# isp.net
KiCad netlist of a schematic drawn in EAGLE
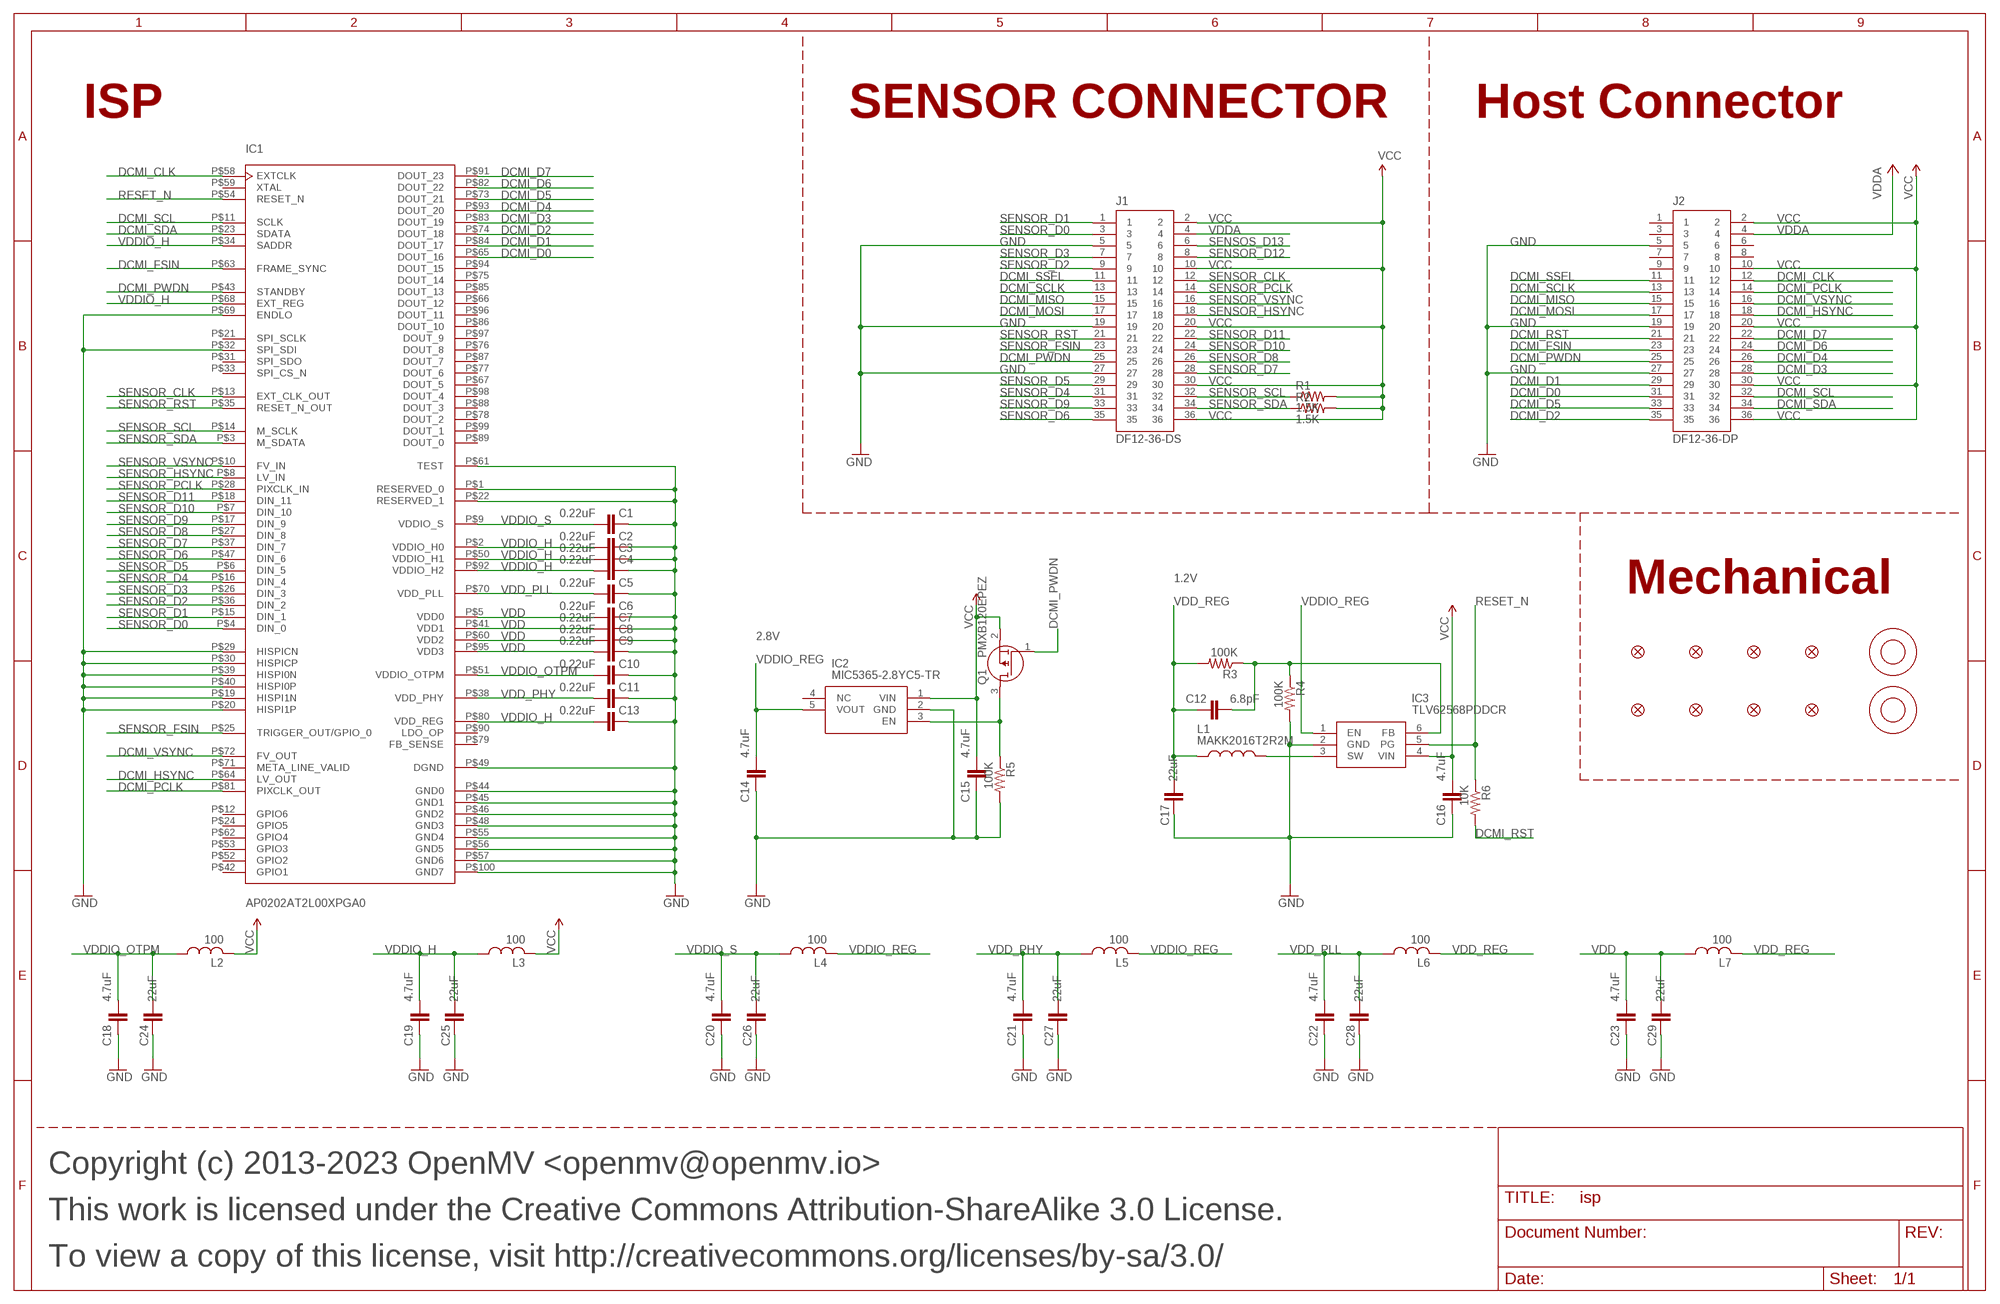
[diagram p0: schematic, sheet 1]

(export (version "E")
  (design (tool "Eeschema 10.0.6"))
  (components
    (comp (ref "C1")
      (value "0.22uF")
      (footprint "eagle-import:C0201")
      (fields (field (name "MPN") "GRM033R60J224ME15D"))
      (libsource (lib "eagle-import") (part "C-EUC0201"))
    )
    (comp (ref "C2")
      (value "0.22uF")
      (footprint "eagle-import:C0201")
      (fields (field (name "MPN") "GRM033R60J224ME15D"))
      (libsource (lib "eagle-import") (part "C-EUC0201"))
    )
    (comp (ref "C3")
      (value "0.22uF")
      (footprint "eagle-import:C0201")
      (fields (field (name "MPN") "GRM033R60J224ME15D"))
      (libsource (lib "eagle-import") (part "C-EUC0201"))
    )
    (comp (ref "C4")
      (value "0.22uF")
      (footprint "eagle-import:C0201")
      (fields (field (name "MPN") "GRM033R60J224ME15D"))
      (libsource (lib "eagle-import") (part "C-EUC0201"))
    )
    (comp (ref "C5")
      (value "0.22uF")
      (footprint "eagle-import:C0201")
      (fields (field (name "MPN") "GRM033R60J224ME15D"))
      (libsource (lib "eagle-import") (part "C-EUC0201"))
    )
    (comp (ref "C6")
      (value "0.22uF")
      (footprint "eagle-import:C0201")
      (fields (field (name "MPN") "GRM033R60J224ME15D"))
      (libsource (lib "eagle-import") (part "C-EUC0201"))
    )
    (comp (ref "C7")
      (value "0.22uF")
      (footprint "eagle-import:C0201")
      (fields (field (name "MPN") "GRM033R60J224ME15D"))
      (libsource (lib "eagle-import") (part "C-EUC0201"))
    )
    (comp (ref "C8")
      (value "0.22uF")
      (footprint "eagle-import:C0201")
      (fields (field (name "MPN") "GRM033R60J224ME15D"))
      (libsource (lib "eagle-import") (part "C-EUC0201"))
    )
    (comp (ref "C9")
      (value "0.22uF")
      (footprint "eagle-import:C0201")
      (fields (field (name "MPN") "GRM033R60J224ME15D"))
      (libsource (lib "eagle-import") (part "C-EUC0201"))
    )
    (comp (ref "C10")
      (value "0.22uF")
      (footprint "eagle-import:C0201")
      (fields (field (name "MPN") "GRM033R60J224ME15D"))
      (libsource (lib "eagle-import") (part "C-EUC0201"))
    )
    (comp (ref "C11")
      (value "0.22uF")
      (footprint "eagle-import:C0201")
      (fields (field (name "MPN") "GRM033R60J224ME15D"))
      (libsource (lib "eagle-import") (part "C-EUC0201"))
    )
    (comp (ref "C12")
      (value "6.8pF")
      (footprint "eagle-import:0402")
      (fields (field (name "MPN") "GRM1555C1H6R8DA01D"))
      (libsource (lib "eagle-import") (part "CAP_0402"))
    )
    (comp (ref "C13")
      (value "0.22uF")
      (footprint "eagle-import:C0201")
      (fields (field (name "MPN") "GRM033R60J224ME15D"))
      (libsource (lib "eagle-import") (part "C-EUC0201"))
    )
    (comp (ref "C14")
      (value "4.7uF")
      (footprint "eagle-import:0402")
      (fields (field (name "MPN") "JMK105BBJ475MV-F"))
      (libsource (lib "eagle-import") (part "CAP_0402"))
    )
    (comp (ref "C15")
      (value "4.7uF")
      (footprint "eagle-import:0402")
      (fields (field (name "MPN") "JMK105BBJ475MV-F"))
      (libsource (lib "eagle-import") (part "CAP_0402"))
    )
    (comp (ref "C16")
      (value "4.7uF")
      (footprint "eagle-import:0402")
      (fields (field (name "MPN") "JMK105BBJ475MV-F"))
      (libsource (lib "eagle-import") (part "CAP_0402"))
    )
    (comp (ref "C17")
      (value "22uF")
      (footprint "eagle-import:0805")
      (fields (field (name "MPN") "CL21A226MQQNNNE"))
      (libsource (lib "eagle-import") (part "22UF-0805-6.3V-20%"))
    )
    (comp (ref "C18")
      (value "4.7uF")
      (footprint "eagle-import:0402")
      (fields (field (name "MPN") "JMK105BBJ475MV-F"))
      (libsource (lib "eagle-import") (part "CAP_0402"))
    )
    (comp (ref "C19")
      (value "4.7uF")
      (footprint "eagle-import:0402")
      (fields (field (name "MPN") "JMK105BBJ475MV-F"))
      (libsource (lib "eagle-import") (part "CAP_0402"))
    )
    (comp (ref "C20")
      (value "4.7uF")
      (footprint "eagle-import:0402")
      (fields (field (name "MPN") "JMK105BBJ475MV-F"))
      (libsource (lib "eagle-import") (part "CAP_0402"))
    )
    (comp (ref "C21")
      (value "4.7uF")
      (footprint "eagle-import:0402")
      (fields (field (name "MPN") "JMK105BBJ475MV-F"))
      (libsource (lib "eagle-import") (part "CAP_0402"))
    )
    (comp (ref "C22")
      (value "4.7uF")
      (footprint "eagle-import:0402")
      (fields (field (name "MPN") "JMK105BBJ475MV-F"))
      (libsource (lib "eagle-import") (part "CAP_0402"))
    )
    (comp (ref "C23")
      (value "4.7uF")
      (footprint "eagle-import:0402")
      (fields (field (name "MPN") "JMK105BBJ475MV-F"))
      (libsource (lib "eagle-import") (part "CAP_0402"))
    )
    (comp (ref "C24")
      (value "22uF")
      (footprint "eagle-import:0805")
      (fields (field (name "MPN") "CL21A226MQQNNNE"))
      (libsource (lib "eagle-import") (part "22UF-0805-6.3V-20%"))
    )
    (comp (ref "C25")
      (value "22uF")
      (footprint "eagle-import:0805")
      (fields (field (name "MPN") "CL21A226MQQNNNE"))
      (libsource (lib "eagle-import") (part "22UF-0805-6.3V-20%"))
    )
    (comp (ref "C26")
      (value "22uF")
      (footprint "eagle-import:0805")
      (fields (field (name "MPN") "CL21A226MQQNNNE"))
      (libsource (lib "eagle-import") (part "22UF-0805-6.3V-20%"))
    )
    (comp (ref "C27")
      (value "22uF")
      (footprint "eagle-import:0805")
      (fields (field (name "MPN") "CL21A226MQQNNNE"))
      (libsource (lib "eagle-import") (part "22UF-0805-6.3V-20%"))
    )
    (comp (ref "C28")
      (value "22uF")
      (footprint "eagle-import:0805")
      (fields (field (name "MPN") "CL21A226MQQNNNE"))
      (libsource (lib "eagle-import") (part "22UF-0805-6.3V-20%"))
    )
    (comp (ref "C29")
      (value "22uF")
      (footprint "eagle-import:0805")
      (fields (field (name "MPN") "CL21A226MQQNNNE"))
      (libsource (lib "eagle-import") (part "22UF-0805-6.3V-20%"))
    )
    (comp (ref "FD1")
      (value "FIDUCIAL1X2")
      (footprint "eagle-import:FIDUCIAL-1X2")
      (libsource (lib "eagle-import") (part "FIDUCIAL1X2"))
    )
    (comp (ref "FD2")
      (value "FIDUCIAL1X2")
      (footprint "eagle-import:FIDUCIAL-1X2")
      (libsource (lib "eagle-import") (part "FIDUCIAL1X2"))
    )
    (comp (ref "FD3")
      (value "FIDUCIAL1X2")
      (footprint "eagle-import:FIDUCIAL-1X2")
      (libsource (lib "eagle-import") (part "FIDUCIAL1X2"))
    )
    (comp (ref "FD4")
      (value "FIDUCIAL1X2")
      (footprint "eagle-import:FIDUCIAL-1X2")
      (libsource (lib "eagle-import") (part "FIDUCIAL1X2"))
    )
    (comp (ref "FD5")
      (value "FIDUCIAL1X2")
      (footprint "eagle-import:FIDUCIAL-1X2")
      (libsource (lib "eagle-import") (part "FIDUCIAL1X2"))
    )
    (comp (ref "FD6")
      (value "FIDUCIAL1X2")
      (footprint "eagle-import:FIDUCIAL-1X2")
      (libsource (lib "eagle-import") (part "FIDUCIAL1X2"))
    )
    (comp (ref "FD7")
      (value "FIDUCIAL1X2")
      (footprint "eagle-import:FIDUCIAL-1X2")
      (libsource (lib "eagle-import") (part "FIDUCIAL1X2"))
    )
    (comp (ref "FD8")
      (value "FIDUCIAL1X2")
      (footprint "eagle-import:FIDUCIAL-1X2")
      (libsource (lib "eagle-import") (part "FIDUCIAL1X2"))
    )
    (comp (ref "IC1")
      (value "AP0202AT2L00XPGA0")
      (footprint "eagle-import:AP0202AT2L00XPGA0")
      (fields (field (name "MPN") "AP0202AT2L00XPGA0-DR"))
      (libsource (lib "eagle-import") (part "AP0202AT2L00XPGA0"))
    )
    (comp (ref "IC2")
      (value "MIC5365-2.8YC5-TR")
      (footprint "eagle-import:SOT65P210X110-5N")
      (fields (field (name "MOUSER_PART_NUMBER") "998-MIC5365-2.8YC5TR"))
      (libsource (lib "eagle-import") (part "MIC5365-2.8YC5-TR"))
    )
    (comp (ref "IC3")
      (value "TLV62568PDDCR")
      (footprint "eagle-import:SOT95P280X110-6N")
      (fields (field (name "MOUSER_PART_NUMBER") "595-TLV62568PDDCR"))
      (libsource (lib "eagle-import") (part "TLV62568PDDCR"))
    )
    (comp (ref "J1")
      (value "DF12-36-DS")
      (footprint "eagle-import:DF12-36-DS")
      (fields (field (name "MPN") "DF12NB-36DS-0.5V(51)"))
      (libsource (lib "eagle-import") (part "DF12-36-DS"))
    )
    (comp (ref "J2")
      (value "DF12-36-DP")
      (footprint "eagle-import:DF12-36-DP")
      (fields (field (name "MPN") "DF12NB(3.0)-36DP-0.5V(51)"))
      (libsource (lib "eagle-import") (part "DF12-36-DP"))
    )
    (comp (ref "L1")
      (value "MAKK2016T2R2M")
      (footprint "eagle-import:INDC2016X100N")
      (fields (field (name "MF") "Taiyo Yuden"))
      (libsource (lib "eagle-import") (part "MAKK2016T2R2M"))
    )
    (comp (ref "L2")
      (value "100")
      (footprint "eagle-import:0402")
      (fields (field (name "MPN") "MFBM1V1005-101-R"))
      (libsource (lib "eagle-import") (part "INDUCTOR_0402"))
    )
    (comp (ref "L3")
      (value "100")
      (footprint "eagle-import:0402")
      (fields (field (name "MPN") "MFBM1V1005-101-R"))
      (libsource (lib "eagle-import") (part "INDUCTOR_0402"))
    )
    (comp (ref "L4")
      (value "100")
      (footprint "eagle-import:0402")
      (fields (field (name "MPN") "MFBM1V1005-101-R"))
      (libsource (lib "eagle-import") (part "INDUCTOR_0402"))
    )
    (comp (ref "L5")
      (value "100")
      (footprint "eagle-import:0402")
      (fields (field (name "MPN") "MFBM1V1005-101-R"))
      (libsource (lib "eagle-import") (part "INDUCTOR_0402"))
    )
    (comp (ref "L6")
      (value "100")
      (footprint "eagle-import:0402")
      (fields (field (name "MPN") "MFBM1V1005-101-R"))
      (libsource (lib "eagle-import") (part "INDUCTOR_0402"))
    )
    (comp (ref "L7")
      (value "100")
      (footprint "eagle-import:0402")
      (fields (field (name "MPN") "MFBM1V1005-101-R"))
      (libsource (lib "eagle-import") (part "INDUCTOR_0402"))
    )
    (comp (ref "M1")
      (value "9774030151R")
      (footprint "eagle-import:9774030151R")
      (libsource (lib "eagle-import") (part "9774030151R"))
    )
    (comp (ref "M2")
      (value "9774030151R")
      (footprint "eagle-import:9774030151R")
      (libsource (lib "eagle-import") (part "9774030151R"))
    )
    (comp (ref "Q1")
      (value "PMXB120EPEZ")
      (footprint "eagle-import:PMXB120EPEZ")
      (fields (field (name "MOUSER_PART_NUMBER") "771-PMXB120EPEZ"))
      (libsource (lib "eagle-import") (part "PMXB120EPEZ"))
    )
    (comp (ref "R1")
      (value "1.5K")
      (footprint "eagle-import:R0402")
      (fields (field (name "MPN") "RC0402FR-131K5L"))
      (libsource (lib "eagle-import") (part "R-US_R0402"))
    )
    (comp (ref "R2")
      (value "1.5K")
      (footprint "eagle-import:R0402")
      (fields (field (name "MPN") "RC0402FR-131K5L"))
      (libsource (lib "eagle-import") (part "R-US_R0402"))
    )
    (comp (ref "R3")
      (value "100K")
      (footprint "eagle-import:R0402")
      (fields (field (name "MPN") "AC0402FR-07100KL"))
      (libsource (lib "eagle-import") (part "R-US_R0402"))
    )
    (comp (ref "R4")
      (value "100K")
      (footprint "eagle-import:R0402")
      (fields (field (name "MPN") "AC0402FR-07100KL"))
      (libsource (lib "eagle-import") (part "R-US_R0402"))
    )
    (comp (ref "R5")
      (value "100K")
      (footprint "eagle-import:R0402")
      (fields (field (name "MPN") "AC0402FR-07100KL"))
      (libsource (lib "eagle-import") (part "R-US_R0402"))
    )
    (comp (ref "R6")
      (value "10K")
      (footprint "eagle-import:R0402")
      (fields (field (name "MPN") "AC0402FR-1310KL"))
      (libsource (lib "eagle-import") (part "R-US_R0402"))
    )
  )
  (nets
    (net (code "1") (name "/DCMI_CLK") (class "Default")
      (node (ref "IC1") (pin "P$58") (pinfunction "EXTCLK_P$58") (pintype "input"))
      (node (ref "J2") (pin "12") (pinfunction "12_12") (pintype "bidirectional"))
    )
    (net (code "2") (name "/DCMI_D0") (class "Default")
      (node (ref "IC1") (pin "P$65") (pinfunction "DOUT_16_P$65") (pintype "output"))
      (node (ref "J2") (pin "31") (pinfunction "31_31") (pintype "bidirectional"))
    )
    (net (code "3") (name "/DCMI_D1") (class "Default")
      (node (ref "IC1") (pin "P$84") (pinfunction "DOUT_17_P$84") (pintype "output"))
      (node (ref "J2") (pin "29") (pinfunction "29_29") (pintype "bidirectional"))
    )
    (net (code "4") (name "/DCMI_D2") (class "Default")
      (node (ref "IC1") (pin "P$74") (pinfunction "DOUT_18_P$74") (pintype "output"))
      (node (ref "J2") (pin "35") (pinfunction "35_35") (pintype "bidirectional"))
    )
    (net (code "5") (name "/DCMI_D3") (class "Default")
      (node (ref "IC1") (pin "P$83") (pinfunction "DOUT_19_P$83") (pintype "output"))
      (node (ref "J2") (pin "28") (pinfunction "28_28") (pintype "bidirectional"))
    )
    (net (code "6") (name "/DCMI_D4") (class "Default")
      (node (ref "IC1") (pin "P$93") (pinfunction "DOUT_20_P$93") (pintype "output"))
      (node (ref "J2") (pin "26") (pinfunction "26_26") (pintype "bidirectional"))
    )
    (net (code "7") (name "/DCMI_D5") (class "Default")
      (node (ref "IC1") (pin "P$73") (pinfunction "DOUT_21_P$73") (pintype "output"))
      (node (ref "J2") (pin "33") (pinfunction "33_33") (pintype "bidirectional"))
    )
    (net (code "8") (name "/DCMI_D6") (class "Default")
      (node (ref "IC1") (pin "P$82") (pinfunction "DOUT_22_P$82") (pintype "output"))
      (node (ref "J2") (pin "24") (pinfunction "24_24") (pintype "bidirectional"))
    )
    (net (code "9") (name "/DCMI_D7") (class "Default")
      (node (ref "IC1") (pin "P$91") (pinfunction "DOUT_23_P$91") (pintype "output"))
      (node (ref "J2") (pin "22") (pinfunction "22_22") (pintype "bidirectional"))
    )
    (net (code "10") (name "/DCMI_FSIN") (class "Default")
      (node (ref "IC1") (pin "P$63") (pinfunction "FRAME_SYNC_P$63") (pintype "input"))
      (node (ref "J2") (pin "23") (pinfunction "23_23") (pintype "bidirectional"))
    )
    (net (code "11") (name "/DCMI_HSYNC") (class "Default")
      (node (ref "IC1") (pin "P$64") (pinfunction "LV_OUT_P$64") (pintype "output"))
      (node (ref "J2") (pin "18") (pinfunction "18_18") (pintype "bidirectional"))
    )
    (net (code "12") (name "/DCMI_MISO") (class "Default")
      (node (ref "J1") (pin "15") (pinfunction "15_15") (pintype "bidirectional"))
      (node (ref "J2") (pin "15") (pinfunction "15_15") (pintype "bidirectional"))
    )
    (net (code "13") (name "/DCMI_MOSI") (class "Default")
      (node (ref "J1") (pin "17") (pinfunction "17_17") (pintype "bidirectional"))
      (node (ref "J2") (pin "17") (pinfunction "17_17") (pintype "bidirectional"))
    )
    (net (code "14") (name "/DCMI_PCLK") (class "Default")
      (node (ref "IC1") (pin "P$81") (pinfunction "PIXCLK_OUT_P$81") (pintype "output"))
      (node (ref "J2") (pin "14") (pinfunction "14_14") (pintype "bidirectional"))
    )
    (net (code "15") (name "/DCMI_PWDN") (class "Default")
      (node (ref "IC1") (pin "P$43") (pinfunction "STANDBY_P$43") (pintype "input"))
      (node (ref "J1") (pin "25") (pinfunction "25_25") (pintype "bidirectional"))
      (node (ref "J2") (pin "25") (pinfunction "25_25") (pintype "bidirectional"))
      (node (ref "Q1") (pin "1") (pinfunction "G_1") (pintype "bidirectional"))
    )
    (net (code "16") (name "/DCMI_RST") (class "Default")
      (node (ref "J2") (pin "21") (pinfunction "21_21") (pintype "bidirectional"))
      (node (ref "R6") (pin "2") (pinfunction "2_2") (pintype "passive"))
    )
    (net (code "17") (name "/DCMI_SCL") (class "Default")
      (node (ref "IC1") (pin "P$11") (pinfunction "SCLK_P$11") (pintype "input"))
      (node (ref "J2") (pin "32") (pinfunction "32_32") (pintype "bidirectional"))
    )
    (net (code "18") (name "/DCMI_SCLK") (class "Default")
      (node (ref "J1") (pin "13") (pinfunction "13_13") (pintype "bidirectional"))
      (node (ref "J2") (pin "13") (pinfunction "13_13") (pintype "bidirectional"))
    )
    (net (code "19") (name "/DCMI_SDA") (class "Default")
      (node (ref "IC1") (pin "P$23") (pinfunction "SDATA_P$23") (pintype "bidirectional"))
      (node (ref "J2") (pin "34") (pinfunction "34_34") (pintype "bidirectional"))
    )
    (net (code "20") (name "/DCMI_SSEL") (class "Default")
      (node (ref "J1") (pin "11") (pinfunction "11_11") (pintype "bidirectional"))
      (node (ref "J2") (pin "11") (pinfunction "11_11") (pintype "bidirectional"))
    )
    (net (code "21") (name "/DCMI_VSYNC") (class "Default")
      (node (ref "IC1") (pin "P$72") (pinfunction "FV_OUT_P$72") (pintype "output"))
      (node (ref "J2") (pin "16") (pinfunction "16_16") (pintype "bidirectional"))
    )
    (net (code "22") (name "/RESET_N") (class "Default")
      (node (ref "IC1") (pin "P$54") (pinfunction "RESET_N_P$54") (pintype "input"))
      (node (ref "IC3") (pin "5") (pinfunction "PG_5") (pintype "bidirectional"))
      (node (ref "R6") (pin "1") (pinfunction "1_1") (pintype "passive"))
    )
    (net (code "23") (name "/SENSOR_CLK") (class "Default")
      (node (ref "IC1") (pin "P$13") (pinfunction "EXT_CLK_OUT_P$13") (pintype "output"))
      (node (ref "J1") (pin "12") (pinfunction "12_12") (pintype "bidirectional"))
    )
    (net (code "24") (name "/SENSOR_D0") (class "Default")
      (node (ref "IC1") (pin "P$4") (pinfunction "DIN_0_P$4") (pintype "input"))
      (node (ref "J1") (pin "3") (pinfunction "3_3") (pintype "bidirectional"))
    )
    (net (code "25") (name "/SENSOR_D1") (class "Default")
      (node (ref "IC1") (pin "P$15") (pinfunction "DIN_1_P$15") (pintype "input"))
      (node (ref "J1") (pin "1") (pinfunction "1_1") (pintype "bidirectional"))
    )
    (net (code "26") (name "/SENSOR_D2") (class "Default")
      (node (ref "IC1") (pin "P$36") (pinfunction "DIN_2_P$36") (pintype "input"))
      (node (ref "J1") (pin "9") (pinfunction "9_9") (pintype "bidirectional"))
    )
    (net (code "27") (name "/SENSOR_D3") (class "Default")
      (node (ref "IC1") (pin "P$26") (pinfunction "DIN_3_P$26") (pintype "input"))
      (node (ref "J1") (pin "7") (pinfunction "7_7") (pintype "bidirectional"))
    )
    (net (code "28") (name "/SENSOR_D4") (class "Default")
      (node (ref "IC1") (pin "P$16") (pinfunction "DIN_4_P$16") (pintype "input"))
      (node (ref "J1") (pin "31") (pinfunction "31_31") (pintype "bidirectional"))
    )
    (net (code "29") (name "/SENSOR_D5") (class "Default")
      (node (ref "IC1") (pin "P$6") (pinfunction "DIN_5_P$6") (pintype "input"))
      (node (ref "J1") (pin "29") (pinfunction "29_29") (pintype "bidirectional"))
    )
    (net (code "30") (name "/SENSOR_D6") (class "Default")
      (node (ref "IC1") (pin "P$47") (pinfunction "DIN_6_P$47") (pintype "input"))
      (node (ref "J1") (pin "35") (pinfunction "35_35") (pintype "bidirectional"))
    )
    (net (code "31") (name "/SENSOR_D7") (class "Default")
      (node (ref "IC1") (pin "P$37") (pinfunction "DIN_7_P$37") (pintype "input"))
      (node (ref "J1") (pin "28") (pinfunction "28_28") (pintype "bidirectional"))
    )
    (net (code "32") (name "/SENSOR_D8") (class "Default")
      (node (ref "IC1") (pin "P$27") (pinfunction "DIN_8_P$27") (pintype "input"))
      (node (ref "J1") (pin "26") (pinfunction "26_26") (pintype "bidirectional"))
    )
    (net (code "33") (name "/SENSOR_D9") (class "Default")
      (node (ref "IC1") (pin "P$17") (pinfunction "DIN_9_P$17") (pintype "input"))
      (node (ref "J1") (pin "33") (pinfunction "33_33") (pintype "bidirectional"))
    )
    (net (code "34") (name "/SENSOR_D10") (class "Default")
      (node (ref "IC1") (pin "P$7") (pinfunction "DIN_10_P$7") (pintype "input"))
      (node (ref "J1") (pin "24") (pinfunction "24_24") (pintype "bidirectional"))
    )
    (net (code "35") (name "/SENSOR_D11") (class "Default")
      (node (ref "IC1") (pin "P$18") (pinfunction "DIN_11_P$18") (pintype "input"))
      (node (ref "J1") (pin "22") (pinfunction "22_22") (pintype "bidirectional"))
    )
    (net (code "36") (name "/SENSOR_D12") (class "Default")
      (node (ref "J1") (pin "8") (pinfunction "8_8") (pintype "bidirectional"))
    )
    (net (code "37") (name "/SENSOR_FSIN") (class "Default")
      (node (ref "IC1") (pin "P$25") (pinfunction "TRIGGER_OUT/GPIO_0_P$25") (pintype "output"))
      (node (ref "J1") (pin "23") (pinfunction "23_23") (pintype "bidirectional"))
    )
    (net (code "38") (name "/SENSOR_HSYNC") (class "Default")
      (node (ref "IC1") (pin "P$8") (pinfunction "LV_IN_P$8") (pintype "input"))
      (node (ref "J1") (pin "18") (pinfunction "18_18") (pintype "bidirectional"))
    )
    (net (code "39") (name "/SENSOR_PCLK") (class "Default")
      (node (ref "IC1") (pin "P$28") (pinfunction "PIXCLK_IN_P$28") (pintype "input"))
      (node (ref "J1") (pin "14") (pinfunction "14_14") (pintype "bidirectional"))
    )
    (net (code "40") (name "/SENSOR_RST") (class "Default")
      (node (ref "IC1") (pin "P$35") (pinfunction "RESET_N_OUT_P$35") (pintype "output"))
      (node (ref "J1") (pin "21") (pinfunction "21_21") (pintype "bidirectional"))
    )
    (net (code "41") (name "/SENSOR_SCL") (class "Default")
      (node (ref "IC1") (pin "P$14") (pinfunction "M_SCLK_P$14") (pintype "output"))
      (node (ref "J1") (pin "32") (pinfunction "32_32") (pintype "bidirectional"))
      (node (ref "R1") (pin "1") (pinfunction "1_1") (pintype "passive"))
    )
    (net (code "42") (name "/SENSOR_SDA") (class "Default")
      (node (ref "IC1") (pin "P$3") (pinfunction "M_SDATA_P$3") (pintype "bidirectional"))
      (node (ref "J1") (pin "34") (pinfunction "34_34") (pintype "bidirectional"))
      (node (ref "R2") (pin "1") (pinfunction "1_1") (pintype "passive"))
    )
    (net (code "43") (name "/SENSOR_VSYNC") (class "Default")
      (node (ref "IC1") (pin "P$10") (pinfunction "FV_IN_P$10") (pintype "input"))
      (node (ref "J1") (pin "16") (pinfunction "16_16") (pintype "bidirectional"))
    )
    (net (code "44") (name "/SENSOS_D13") (class "Default")
      (node (ref "J1") (pin "6") (pinfunction "6_6") (pintype "bidirectional"))
    )
    (net (code "45") (name "/VDD") (class "Default")
      (node (ref "C23") (pin "2") (pinfunction "2_2") (pintype "passive"))
      (node (ref "C29") (pin "2") (pinfunction "2_2") (pintype "passive"))
      (node (ref "C6") (pin "2") (pinfunction "2_2") (pintype "passive"))
      (node (ref "C7") (pin "2") (pinfunction "2_2") (pintype "passive"))
      (node (ref "C8") (pin "2") (pinfunction "2_2") (pintype "passive"))
      (node (ref "C9") (pin "2") (pinfunction "2_2") (pintype "passive"))
      (node (ref "IC1") (pin "P$41") (pinfunction "VDD1_P$41") (pintype "power_in"))
      (node (ref "IC1") (pin "P$5") (pinfunction "VDD0_P$5") (pintype "power_in"))
      (node (ref "IC1") (pin "P$60") (pinfunction "VDD2_P$60") (pintype "power_in"))
      (node (ref "IC1") (pin "P$95") (pinfunction "VDD3_P$95") (pintype "power_in"))
      (node (ref "L7") (pin "1") (pinfunction "P$1_1") (pintype "passive"))
    )
    (net (code "46") (name "/VDDIO_H") (class "Default")
      (node (ref "C13") (pin "2") (pinfunction "2_2") (pintype "passive"))
      (node (ref "C19") (pin "2") (pinfunction "2_2") (pintype "passive"))
      (node (ref "C2") (pin "2") (pinfunction "2_2") (pintype "passive"))
      (node (ref "C25") (pin "2") (pinfunction "2_2") (pintype "passive"))
      (node (ref "C3") (pin "2") (pinfunction "2_2") (pintype "passive"))
      (node (ref "C4") (pin "2") (pinfunction "2_2") (pintype "passive"))
      (node (ref "IC1") (pin "P$2") (pinfunction "VDDIO_H0_P$2") (pintype "power_in"))
      (node (ref "IC1") (pin "P$34") (pinfunction "SADDR_P$34") (pintype "input"))
      (node (ref "IC1") (pin "P$50") (pinfunction "VDDIO_H1_P$50") (pintype "power_in"))
      (node (ref "IC1") (pin "P$68") (pinfunction "EXT_REG_P$68") (pintype "input"))
      (node (ref "IC1") (pin "P$80") (pinfunction "VDD_REG_P$80") (pintype "power_in"))
      (node (ref "IC1") (pin "P$92") (pinfunction "VDDIO_H2_P$92") (pintype "power_in"))
      (node (ref "L3") (pin "1") (pinfunction "P$1_1") (pintype "passive"))
    )
    (net (code "47") (name "/VDDIO_OTPM") (class "Default")
      (node (ref "C10") (pin "2") (pinfunction "2_2") (pintype "passive"))
      (node (ref "C18") (pin "2") (pinfunction "2_2") (pintype "passive"))
      (node (ref "C24") (pin "2") (pinfunction "2_2") (pintype "passive"))
      (node (ref "IC1") (pin "P$51") (pinfunction "VDDIO_OTPM_P$51") (pintype "power_in"))
      (node (ref "L2") (pin "1") (pinfunction "P$1_1") (pintype "passive"))
    )
    (net (code "48") (name "/VDDIO_REG") (class "Default")
      (node (ref "C14") (pin "2") (pinfunction "2_2") (pintype "passive"))
      (node (ref "IC2") (pin "5") (pinfunction "VOUT_5") (pintype "bidirectional"))
      (node (ref "IC3") (pin "1") (pinfunction "EN_1") (pintype "bidirectional"))
      (node (ref "L4") (pin "2") (pinfunction "P$2_2") (pintype "passive"))
      (node (ref "L5") (pin "2") (pinfunction "P$2_2") (pintype "passive"))
    )
    (net (code "49") (name "/VDDIO_S") (class "Default")
      (node (ref "C1") (pin "2") (pinfunction "2_2") (pintype "passive"))
      (node (ref "C20") (pin "2") (pinfunction "2_2") (pintype "passive"))
      (node (ref "C26") (pin "2") (pinfunction "2_2") (pintype "passive"))
      (node (ref "IC1") (pin "P$9") (pinfunction "VDDIO_S_P$9") (pintype "power_in"))
      (node (ref "L4") (pin "1") (pinfunction "P$1_1") (pintype "passive"))
    )
    (net (code "50") (name "/VDD_PHY") (class "Default")
      (node (ref "C11") (pin "2") (pinfunction "2_2") (pintype "passive"))
      (node (ref "C21") (pin "2") (pinfunction "2_2") (pintype "passive"))
      (node (ref "C27") (pin "2") (pinfunction "2_2") (pintype "passive"))
      (node (ref "IC1") (pin "P$38") (pinfunction "VDD_PHY_P$38") (pintype "power_in"))
      (node (ref "L5") (pin "1") (pinfunction "P$1_1") (pintype "passive"))
    )
    (net (code "51") (name "/VDD_PLL") (class "Default")
      (node (ref "C22") (pin "2") (pinfunction "2_2") (pintype "passive"))
      (node (ref "C28") (pin "2") (pinfunction "2_2") (pintype "passive"))
      (node (ref "C5") (pin "2") (pinfunction "2_2") (pintype "passive"))
      (node (ref "IC1") (pin "P$70") (pinfunction "VDD_PLL_P$70") (pintype "power_in"))
      (node (ref "L6") (pin "1") (pinfunction "P$1_1") (pintype "passive"))
    )
    (net (code "52") (name "/VDD_REG") (class "Default")
      (node (ref "C12") (pin "1") (pinfunction "1_1") (pintype "passive"))
      (node (ref "C17") (pin "2") (pinfunction "2_2") (pintype "passive"))
      (node (ref "L1") (pin "1") (pinfunction "1_1") (pintype "passive"))
      (node (ref "L6") (pin "2") (pinfunction "P$2_2") (pintype "passive"))
      (node (ref "L7") (pin "2") (pinfunction "P$2_2") (pintype "passive"))
      (node (ref "R3") (pin "2") (pinfunction "2_2") (pintype "passive"))
    )
    (net (code "53") (name "GND") (class "Default")
      (node (ref "C1") (pin "1") (pinfunction "1_1") (pintype "passive"))
      (node (ref "C10") (pin "1") (pinfunction "1_1") (pintype "passive"))
      (node (ref "C11") (pin "1") (pinfunction "1_1") (pintype "passive"))
      (node (ref "C13") (pin "1") (pinfunction "1_1") (pintype "passive"))
      (node (ref "C14") (pin "1") (pinfunction "1_1") (pintype "passive"))
      (node (ref "C15") (pin "1") (pinfunction "1_1") (pintype "passive"))
      (node (ref "C16") (pin "1") (pinfunction "1_1") (pintype "passive"))
      (node (ref "C17") (pin "1") (pinfunction "1_1") (pintype "passive"))
      (node (ref "C18") (pin "1") (pinfunction "1_1") (pintype "passive"))
      (node (ref "C19") (pin "1") (pinfunction "1_1") (pintype "passive"))
      (node (ref "C2") (pin "1") (pinfunction "1_1") (pintype "passive"))
      (node (ref "C20") (pin "1") (pinfunction "1_1") (pintype "passive"))
      (node (ref "C21") (pin "1") (pinfunction "1_1") (pintype "passive"))
      (node (ref "C22") (pin "1") (pinfunction "1_1") (pintype "passive"))
      (node (ref "C23") (pin "1") (pinfunction "1_1") (pintype "passive"))
      (node (ref "C24") (pin "1") (pinfunction "1_1") (pintype "passive"))
      (node (ref "C25") (pin "1") (pinfunction "1_1") (pintype "passive"))
      (node (ref "C26") (pin "1") (pinfunction "1_1") (pintype "passive"))
      (node (ref "C27") (pin "1") (pinfunction "1_1") (pintype "passive"))
      (node (ref "C28") (pin "1") (pinfunction "1_1") (pintype "passive"))
      (node (ref "C29") (pin "1") (pinfunction "1_1") (pintype "passive"))
      (node (ref "C3") (pin "1") (pinfunction "1_1") (pintype "passive"))
      (node (ref "C4") (pin "1") (pinfunction "1_1") (pintype "passive"))
      (node (ref "C5") (pin "1") (pinfunction "1_1") (pintype "passive"))
      (node (ref "C6") (pin "1") (pinfunction "1_1") (pintype "passive"))
      (node (ref "C7") (pin "1") (pinfunction "1_1") (pintype "passive"))
      (node (ref "C8") (pin "1") (pinfunction "1_1") (pintype "passive"))
      (node (ref "C9") (pin "1") (pinfunction "1_1") (pintype "passive"))
      (node (ref "IC1") (pin "P$1") (pinfunction "RESERVED_0_P$1") (pintype "input"))
      (node (ref "IC1") (pin "P$100") (pinfunction "GND7_P$100") (pintype "power_in"))
      (node (ref "IC1") (pin "P$19") (pinfunction "HISPI1N_P$19") (pintype "input"))
      (node (ref "IC1") (pin "P$20") (pinfunction "HISPI1P_P$20") (pintype "input"))
      (node (ref "IC1") (pin "P$22") (pinfunction "RESERVED_1_P$22") (pintype "input"))
      (node (ref "IC1") (pin "P$29") (pinfunction "HISPICN_P$29") (pintype "input"))
      (node (ref "IC1") (pin "P$30") (pinfunction "HISPICP_P$30") (pintype "input"))
      (node (ref "IC1") (pin "P$32") (pinfunction "SPI_SDI_P$32") (pintype "input"))
      (node (ref "IC1") (pin "P$39") (pinfunction "HISPI0N_P$39") (pintype "input"))
      (node (ref "IC1") (pin "P$40") (pinfunction "HISPI0P_P$40") (pintype "input"))
      (node (ref "IC1") (pin "P$44") (pinfunction "GND0_P$44") (pintype "power_in"))
      (node (ref "IC1") (pin "P$45") (pinfunction "GND1_P$45") (pintype "power_in"))
      (node (ref "IC1") (pin "P$46") (pinfunction "GND2_P$46") (pintype "power_in"))
      (node (ref "IC1") (pin "P$48") (pinfunction "GND3_P$48") (pintype "power_in"))
      (node (ref "IC1") (pin "P$49") (pinfunction "DGND_P$49") (pintype "power_in"))
      (node (ref "IC1") (pin "P$55") (pinfunction "GND4_P$55") (pintype "power_in"))
      (node (ref "IC1") (pin "P$56") (pinfunction "GND5_P$56") (pintype "power_in"))
      (node (ref "IC1") (pin "P$57") (pinfunction "GND6_P$57") (pintype "power_in"))
      (node (ref "IC1") (pin "P$61") (pinfunction "TEST_P$61") (pintype "input"))
      (node (ref "IC1") (pin "P$69") (pinfunction "ENDLO_P$69") (pintype "input"))
      (node (ref "IC2") (pin "2") (pinfunction "GND_2") (pintype "bidirectional"))
      (node (ref "IC3") (pin "2") (pinfunction "GND_2") (pintype "bidirectional"))
      (node (ref "J1") (pin "19") (pinfunction "19_19") (pintype "bidirectional"))
      (node (ref "J1") (pin "27") (pinfunction "27_27") (pintype "bidirectional"))
      (node (ref "J1") (pin "5") (pinfunction "5_5") (pintype "bidirectional"))
      (node (ref "J2") (pin "19") (pinfunction "19_19") (pintype "bidirectional"))
      (node (ref "J2") (pin "27") (pinfunction "27_27") (pintype "bidirectional"))
      (node (ref "J2") (pin "5") (pinfunction "5_5") (pintype "bidirectional"))
      (node (ref "R4") (pin "2") (pinfunction "2_2") (pintype "passive"))
      (node (ref "R5") (pin "2") (pinfunction "2_2") (pintype "passive"))
    )
    (net (code "54") (name "Net-(IC2-EN)") (class "Default")
      (node (ref "IC2") (pin "3") (pinfunction "EN_3") (pintype "bidirectional"))
      (node (ref "Q1") (pin "3") (pinfunction "D_3") (pintype "bidirectional"))
      (node (ref "R5") (pin "1") (pinfunction "1_1") (pintype "passive"))
    )
    (net (code "55") (name "Net-(IC3-FB)") (class "Default")
      (node (ref "C12") (pin "2") (pinfunction "2_2") (pintype "passive"))
      (node (ref "IC3") (pin "6") (pinfunction "FB_6") (pintype "bidirectional"))
      (node (ref "R3") (pin "1") (pinfunction "1_1") (pintype "passive"))
      (node (ref "R4") (pin "1") (pinfunction "1_1") (pintype "passive"))
    )
    (net (code "56") (name "Net-(IC3-SW)") (class "Default")
      (node (ref "IC3") (pin "3") (pinfunction "SW_3") (pintype "bidirectional"))
      (node (ref "L1") (pin "2") (pinfunction "2_2") (pintype "passive"))
    )
    (net (code "57") (name "VCC") (class "Default")
      (node (ref "C15") (pin "2") (pinfunction "2_2") (pintype "passive"))
      (node (ref "C16") (pin "2") (pinfunction "2_2") (pintype "passive"))
      (node (ref "IC2") (pin "1") (pinfunction "VIN_1") (pintype "bidirectional"))
      (node (ref "IC3") (pin "4") (pinfunction "VIN_4") (pintype "bidirectional"))
      (node (ref "J1") (pin "10") (pinfunction "10_10") (pintype "bidirectional"))
      (node (ref "J1") (pin "2") (pinfunction "2_2") (pintype "bidirectional"))
      (node (ref "J1") (pin "20") (pinfunction "20_20") (pintype "bidirectional"))
      (node (ref "J1") (pin "30") (pinfunction "30_30") (pintype "bidirectional"))
      (node (ref "J1") (pin "36") (pinfunction "36_36") (pintype "bidirectional"))
      (node (ref "J2") (pin "10") (pinfunction "10_10") (pintype "bidirectional"))
      (node (ref "J2") (pin "2") (pinfunction "2_2") (pintype "bidirectional"))
      (node (ref "J2") (pin "20") (pinfunction "20_20") (pintype "bidirectional"))
      (node (ref "J2") (pin "30") (pinfunction "30_30") (pintype "bidirectional"))
      (node (ref "J2") (pin "36") (pinfunction "36_36") (pintype "bidirectional"))
      (node (ref "L2") (pin "2") (pinfunction "P$2_2") (pintype "passive"))
      (node (ref "L3") (pin "2") (pinfunction "P$2_2") (pintype "passive"))
      (node (ref "Q1") (pin "2") (pinfunction "S_2") (pintype "bidirectional"))
      (node (ref "R1") (pin "2") (pinfunction "2_2") (pintype "passive"))
      (node (ref "R2") (pin "2") (pinfunction "2_2") (pintype "passive"))
    )
    (net (code "58") (name "VDDA") (class "Default")
      (node (ref "J1") (pin "4") (pinfunction "4_4") (pintype "bidirectional"))
      (node (ref "J2") (pin "4") (pinfunction "4_4") (pintype "bidirectional"))
    )
    (net (code "59") (name "unconnected-(IC1-DOUT_0-PadP$89)") (class "Default")
      (node (ref "IC1") (pin "P$89") (pinfunction "DOUT_0_P$89") (pintype "output"))
    )
    (net (code "60") (name "unconnected-(IC1-DOUT_1-PadP$99)") (class "Default")
      (node (ref "IC1") (pin "P$99") (pinfunction "DOUT_1_P$99") (pintype "output"))
    )
    (net (code "61") (name "unconnected-(IC1-DOUT_2-PadP$78)") (class "Default")
      (node (ref "IC1") (pin "P$78") (pinfunction "DOUT_2_P$78") (pintype "output"))
    )
    (net (code "62") (name "unconnected-(IC1-DOUT_3-PadP$88)") (class "Default")
      (node (ref "IC1") (pin "P$88") (pinfunction "DOUT_3_P$88") (pintype "output"))
    )
    (net (code "63") (name "unconnected-(IC1-DOUT_4-PadP$98)") (class "Default")
      (node (ref "IC1") (pin "P$98") (pinfunction "DOUT_4_P$98") (pintype "output"))
    )
    (net (code "64") (name "unconnected-(IC1-DOUT_5-PadP$67)") (class "Default")
      (node (ref "IC1") (pin "P$67") (pinfunction "DOUT_5_P$67") (pintype "output"))
    )
    (net (code "65") (name "unconnected-(IC1-DOUT_6-PadP$77)") (class "Default")
      (node (ref "IC1") (pin "P$77") (pinfunction "DOUT_6_P$77") (pintype "output"))
    )
    (net (code "66") (name "unconnected-(IC1-DOUT_7-PadP$87)") (class "Default")
      (node (ref "IC1") (pin "P$87") (pinfunction "DOUT_7_P$87") (pintype "output"))
    )
    (net (code "67") (name "unconnected-(IC1-DOUT_8-PadP$76)") (class "Default")
      (node (ref "IC1") (pin "P$76") (pinfunction "DOUT_8_P$76") (pintype "output"))
    )
    (net (code "68") (name "unconnected-(IC1-DOUT_9-PadP$97)") (class "Default")
      (node (ref "IC1") (pin "P$97") (pinfunction "DOUT_9_P$97") (pintype "output"))
    )
    (net (code "69") (name "unconnected-(IC1-DOUT_10-PadP$86)") (class "Default")
      (node (ref "IC1") (pin "P$86") (pinfunction "DOUT_10_P$86") (pintype "output"))
    )
    (net (code "70") (name "unconnected-(IC1-DOUT_11-PadP$96)") (class "Default")
      (node (ref "IC1") (pin "P$96") (pinfunction "DOUT_11_P$96") (pintype "output"))
    )
    (net (code "71") (name "unconnected-(IC1-DOUT_12-PadP$66)") (class "Default")
      (node (ref "IC1") (pin "P$66") (pinfunction "DOUT_12_P$66") (pintype "output"))
    )
    (net (code "72") (name "unconnected-(IC1-DOUT_13-PadP$85)") (class "Default")
      (node (ref "IC1") (pin "P$85") (pinfunction "DOUT_13_P$85") (pintype "output"))
    )
    (net (code "73") (name "unconnected-(IC1-DOUT_14-PadP$75)") (class "Default")
      (node (ref "IC1") (pin "P$75") (pinfunction "DOUT_14_P$75") (pintype "output"))
    )
    (net (code "74") (name "unconnected-(IC1-DOUT_15-PadP$94)") (class "Default")
      (node (ref "IC1") (pin "P$94") (pinfunction "DOUT_15_P$94") (pintype "output"))
    )
    (net (code "75") (name "unconnected-(IC1-FB_SENSE-PadP$79)") (class "Default")
      (node (ref "IC1") (pin "P$79") (pinfunction "FB_SENSE_P$79") (pintype "input"))
    )
    (net (code "76") (name "unconnected-(IC1-GPIO1-PadP$42)") (class "Default")
      (node (ref "IC1") (pin "P$42") (pinfunction "GPIO1_P$42") (pintype "bidirectional"))
    )
    (net (code "77") (name "unconnected-(IC1-GPIO2-PadP$52)") (class "Default")
      (node (ref "IC1") (pin "P$52") (pinfunction "GPIO2_P$52") (pintype "bidirectional"))
    )
    (net (code "78") (name "unconnected-(IC1-GPIO3-PadP$53)") (class "Default")
      (node (ref "IC1") (pin "P$53") (pinfunction "GPIO3_P$53") (pintype "bidirectional"))
    )
    (net (code "79") (name "unconnected-(IC1-GPIO4-PadP$62)") (class "Default")
      (node (ref "IC1") (pin "P$62") (pinfunction "GPIO4_P$62") (pintype "bidirectional"))
    )
    (net (code "80") (name "unconnected-(IC1-GPIO5-PadP$24)") (class "Default")
      (node (ref "IC1") (pin "P$24") (pinfunction "GPIO5_P$24") (pintype "bidirectional"))
    )
    (net (code "81") (name "unconnected-(IC1-GPIO6-PadP$12)") (class "Default")
      (node (ref "IC1") (pin "P$12") (pinfunction "GPIO6_P$12") (pintype "bidirectional"))
    )
    (net (code "82") (name "unconnected-(IC1-LDO_OP-PadP$90)") (class "Default")
      (node (ref "IC1") (pin "P$90") (pinfunction "LDO_OP_P$90") (pintype "output"))
    )
    (net (code "83") (name "unconnected-(IC1-META_LINE_VALID-PadP$71)") (class "Default")
      (node (ref "IC1") (pin "P$71") (pinfunction "META_LINE_VALID_P$71") (pintype "output"))
    )
    (net (code "84") (name "unconnected-(IC1-SPI_CS_N-PadP$33)") (class "Default")
      (node (ref "IC1") (pin "P$33") (pinfunction "SPI_CS_N_P$33") (pintype "output"))
    )
    (net (code "85") (name "unconnected-(IC1-SPI_SCLK-PadP$21)") (class "Default")
      (node (ref "IC1") (pin "P$21") (pinfunction "SPI_SCLK_P$21") (pintype "output"))
    )
    (net (code "86") (name "unconnected-(IC1-SPI_SDO-PadP$31)") (class "Default")
      (node (ref "IC1") (pin "P$31") (pinfunction "SPI_SDO_P$31") (pintype "output"))
    )
    (net (code "87") (name "unconnected-(IC1-XTAL-PadP$59)") (class "Default")
      (node (ref "IC1") (pin "P$59") (pinfunction "XTAL_P$59") (pintype "output"))
    )
    (net (code "88") (name "unconnected-(IC2-NC-Pad4)") (class "Default")
      (node (ref "IC2") (pin "4") (pinfunction "NC_4") (pintype "no_connect"))
    )
    (net (code "89") (name "unconnected-(J2-Pad1)") (class "Default")
      (node (ref "J2") (pin "1") (pinfunction "1_1") (pintype "bidirectional"))
    )
    (net (code "90") (name "unconnected-(J2-Pad3)") (class "Default")
      (node (ref "J2") (pin "3") (pinfunction "3_3") (pintype "bidirectional"))
    )
    (net (code "91") (name "unconnected-(J2-Pad6)") (class "Default")
      (node (ref "J2") (pin "6") (pinfunction "6_6") (pintype "bidirectional"))
    )
    (net (code "92") (name "unconnected-(J2-Pad7)") (class "Default")
      (node (ref "J2") (pin "7") (pinfunction "7_7") (pintype "bidirectional"))
    )
    (net (code "93") (name "unconnected-(J2-Pad8)") (class "Default")
      (node (ref "J2") (pin "8") (pinfunction "8_8") (pintype "bidirectional"))
    )
    (net (code "94") (name "unconnected-(J2-Pad9)") (class "Default")
      (node (ref "J2") (pin "9") (pinfunction "9_9") (pintype "bidirectional"))
    )
  )
)
